# avga_final.net
KiCad netlist of a schematic drawn in EAGLE
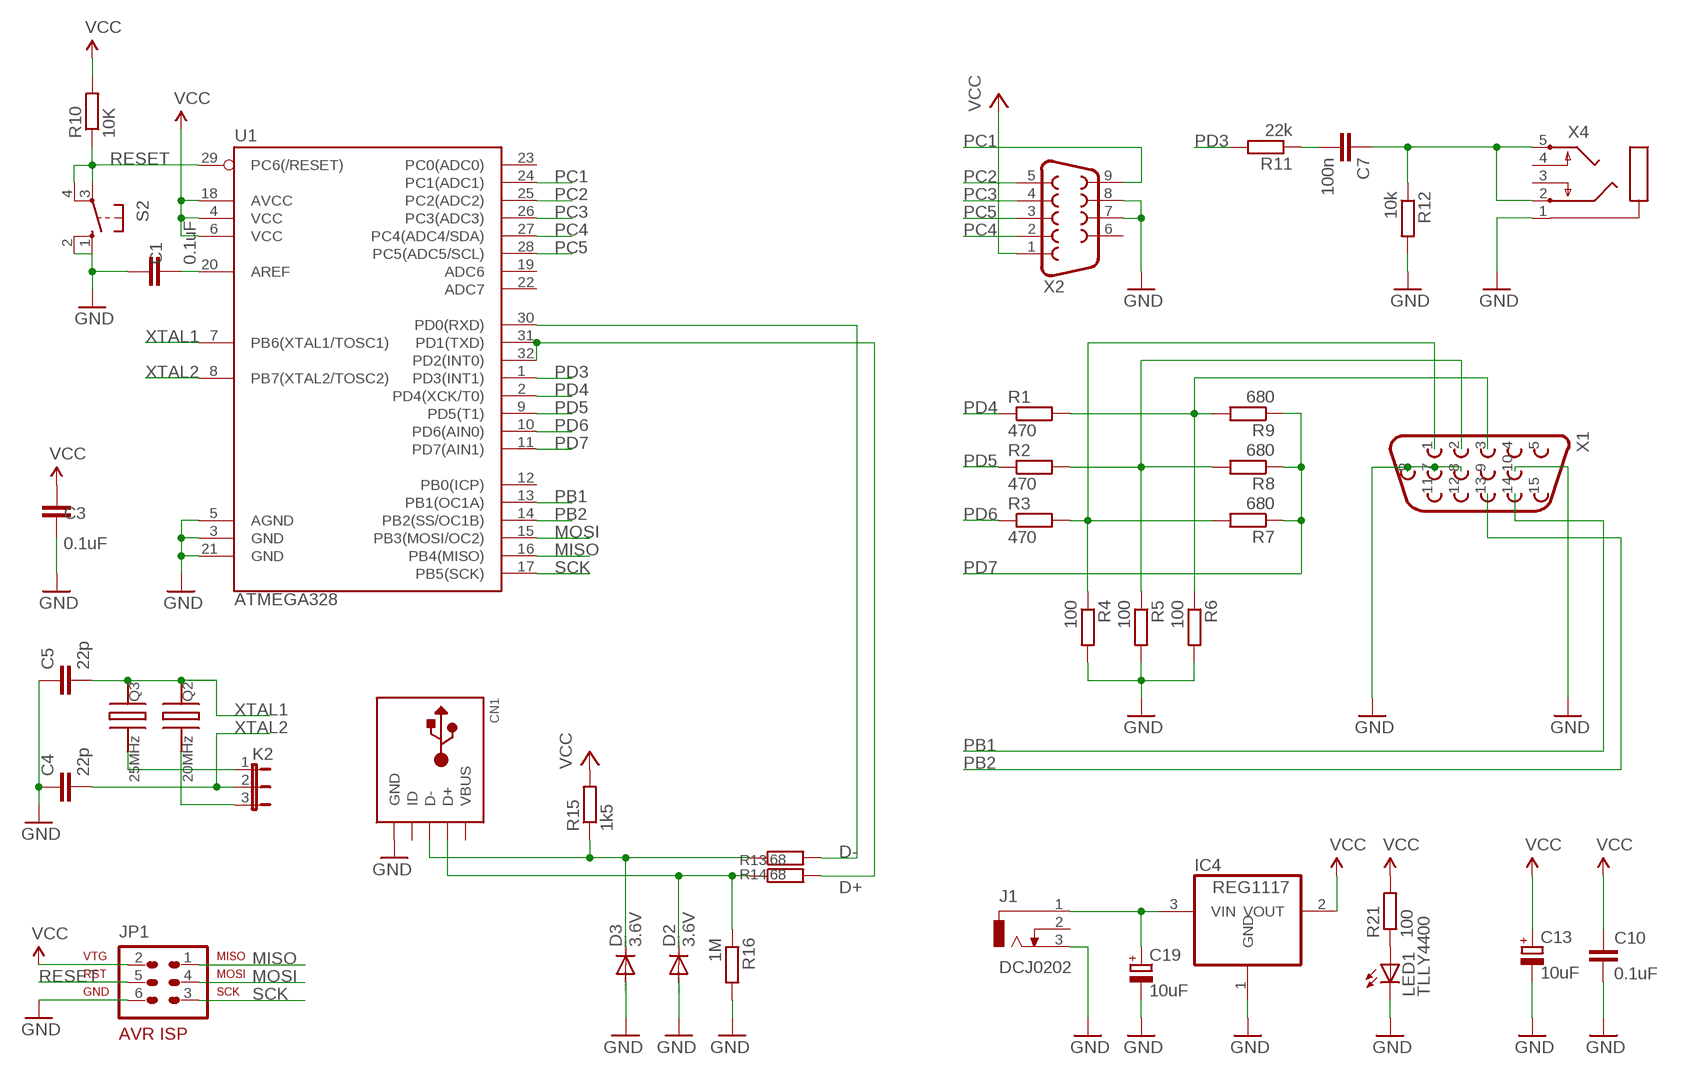
[diagram p0: schematic, sheet 1]

(export (version "E")
  (design (tool "Eeschema 10.0.6"))
  (components
    (comp (ref "C1")
      (value "0.1uF")
      (footprint "eagle-import:C0805")
      (libsource (lib "eagle-import") (part "resistor_C-EUC0805"))
    )
    (comp (ref "C3")
      (value "0.1uF")
      (footprint "eagle-import:C0805")
      (libsource (lib "eagle-import") (part "resistor_C-EUC0805"))
    )
    (comp (ref "C4")
      (value "22p")
      (footprint "eagle-import:C0805")
      (libsource (lib "eagle-import") (part "C-EUC0805"))
    )
    (comp (ref "C5")
      (value "22p")
      (footprint "eagle-import:C0805")
      (libsource (lib "eagle-import") (part "C-EUC0805"))
    )
    (comp (ref "C7")
      (value "100n")
      (footprint "eagle-import:C0805")
      (libsource (lib "eagle-import") (part "C-EUC0805"))
    )
    (comp (ref "C10")
      (value "0.1uF")
      (footprint "eagle-import:C0805")
      (libsource (lib "eagle-import") (part "C-EUC0805"))
    )
    (comp (ref "C13")
      (value "10uF")
      (footprint "eagle-import:E2,5-5")
      (libsource (lib "eagle-import") (part "CPOL-EUE2.5-5"))
    )
    (comp (ref "C19")
      (value "10uF")
      (footprint "eagle-import:E2,5-5")
      (libsource (lib "eagle-import") (part "CPOL-EUE2.5-5"))
    )
    (comp (ref "CN1")
      (value "USBMINIB")
      (footprint "eagle-import:USB-MINIB")
      (libsource (lib "eagle-import") (part "USBMINIB"))
    )
    (comp (ref "D2")
      (value "3.6V")
      (footprint "eagle-import:MINIMELF")
      (libsource (lib "eagle-import") (part "DIODE-MINIMELF"))
    )
    (comp (ref "D3")
      (value "3.6V")
      (footprint "eagle-import:MINIMELF")
      (libsource (lib "eagle-import") (part "DIODE-MINIMELF"))
    )
    (comp (ref "IC4")
      (value "REG1117")
      (footprint "eagle-import:SOT223")
      (libsource (lib "eagle-import") (part "REG1117"))
    )
    (comp (ref "J1")
      (value "DCJ0202")
      (footprint "eagle-import:DCJ0202")
      (libsource (lib "eagle-import") (part "DCJ0202"))
    )
    (comp (ref "JP1")
      (value "AVR-ISP-6R")
      (footprint "eagle-import:AVR-ISP-6R")
      (libsource (lib "eagle-import") (part "AVR-ISP-6R"))
    )
    (comp (ref "K2")
      (value "CON-3-POL")
      (footprint "eagle-import:MOLEX-PSK-03")
      (libsource (lib "eagle-import") (part "CON-3-POL"))
    )
    (comp (ref "LED1")
      (value "TLLY4400")
      (footprint "eagle-import:LED3MM")
      (fields (field (name "MF") "VISHAY SEMICONDUCTOR"))
      (libsource (lib "eagle-import") (part "TLLY4400"))
    )
    (comp (ref "Q2")
      (value "20MHz")
      (footprint "eagle-import:QUARZ")
      (libsource (lib "eagle-import") (part "QUARZ"))
    )
    (comp (ref "Q3")
      (value "25MHz")
      (footprint "eagle-import:QUARZ")
      (libsource (lib "eagle-import") (part "QUARZ"))
    )
    (comp (ref "R1")
      (value "470")
      (footprint "eagle-import:R0805")
      (libsource (lib "eagle-import") (part "R-EU_R0805"))
    )
    (comp (ref "R2")
      (value "470")
      (footprint "eagle-import:R0805")
      (libsource (lib "eagle-import") (part "R-EU_R0805"))
    )
    (comp (ref "R3")
      (value "470")
      (footprint "eagle-import:R0805")
      (libsource (lib "eagle-import") (part "R-EU_R0805"))
    )
    (comp (ref "R4")
      (value "100")
      (footprint "eagle-import:R0805")
      (libsource (lib "eagle-import") (part "R-EU_R0805"))
    )
    (comp (ref "R5")
      (value "100")
      (footprint "eagle-import:R0805")
      (libsource (lib "eagle-import") (part "R-EU_R0805"))
    )
    (comp (ref "R6")
      (value "100")
      (footprint "eagle-import:R0805")
      (libsource (lib "eagle-import") (part "R-EU_R0805"))
    )
    (comp (ref "R7")
      (value "680")
      (footprint "eagle-import:R0805")
      (libsource (lib "eagle-import") (part "R-EU_R0805"))
    )
    (comp (ref "R8")
      (value "680")
      (footprint "eagle-import:R0805")
      (libsource (lib "eagle-import") (part "R-EU_R0805"))
    )
    (comp (ref "R9")
      (value "680")
      (footprint "eagle-import:R0805")
      (libsource (lib "eagle-import") (part "R-EU_R0805"))
    )
    (comp (ref "R10")
      (value "10K")
      (footprint "eagle-import:R0805")
      (libsource (lib "eagle-import") (part "resistor_R-EU_R0805"))
    )
    (comp (ref "R11")
      (value "22k")
      (footprint "eagle-import:R0805")
      (libsource (lib "eagle-import") (part "R-EU_R0805"))
    )
    (comp (ref "R12")
      (value "10k")
      (footprint "eagle-import:R0805")
      (libsource (lib "eagle-import") (part "R-EU_R0805"))
    )
    (comp (ref "R13")
      (value "68")
      (footprint "eagle-import:R0805")
      (libsource (lib "eagle-import") (part "R-EU_R0805"))
    )
    (comp (ref "R14")
      (value "68")
      (footprint "eagle-import:R0805")
      (libsource (lib "eagle-import") (part "R-EU_R0805"))
    )
    (comp (ref "R15")
      (value "1k5")
      (footprint "eagle-import:R0805")
      (libsource (lib "eagle-import") (part "R-EU_R0805"))
    )
    (comp (ref "R16")
      (value "1M")
      (footprint "eagle-import:R0805")
      (libsource (lib "eagle-import") (part "R-EU_R0805"))
    )
    (comp (ref "R21")
      (value "100")
      (footprint "eagle-import:R0805")
      (libsource (lib "eagle-import") (part "resistor_R-EU_R0805"))
    )
    (comp (ref "S2")
      (value "10-XX")
      (footprint "eagle-import:B3F-10XX")
      (fields (field (name "MPN") "B3F-1000"))
      (libsource (lib "eagle-import") (part "10-XX"))
    )
    (comp (ref "U1")
      (value "ATMEGA328")
      (footprint "eagle-import:TQFP32-08")
      (libsource (lib "eagle-import") (part "ATMEGA168"))
    )
    (comp (ref "X1")
      (value "VGA-BU-15POL")
      (footprint "eagle-import:VGA-BU-15POL")
      (libsource (lib "eagle-import") (part "VGA-BU-15POL"))
    )
    (comp (ref "X2")
      (value "D-SUB-ST-9POL")
      (footprint "eagle-import:M09HP")
      (libsource (lib "eagle-import") (part "D-SUB-ST-9POL"))
    )
    (comp (ref "X4")
      (value "KLINKENBUCHSE")
      (footprint "eagle-import:KLINKENBUCHSE")
      (libsource (lib "eagle-import") (part "KLINKENBUCHSE"))
    )
  )
  (nets
    (net (code "1") (name "/MISO") (class "Default")
      (node (ref "JP1") (pin "1") (pinfunction "1_1") (pintype "passive"))
      (node (ref "U1") (pin "16") (pinfunction "PB4(MISO)_16") (pintype "bidirectional"))
    )
    (net (code "2") (name "/MOSI") (class "Default")
      (node (ref "JP1") (pin "4") (pinfunction "4_4") (pintype "passive"))
      (node (ref "U1") (pin "15") (pinfunction "PB3(MOSI/OC2)_15") (pintype "bidirectional"))
    )
    (net (code "3") (name "/PB1") (class "Default")
      (node (ref "U1") (pin "13") (pinfunction "PB1(OC1A)_13") (pintype "bidirectional"))
      (node (ref "X1") (pin "14") (pinfunction "14_14") (pintype "passive"))
    )
    (net (code "4") (name "/PB2") (class "Default")
      (node (ref "U1") (pin "14") (pinfunction "PB2(SS/OC1B)_14") (pintype "bidirectional"))
      (node (ref "X1") (pin "13") (pinfunction "13_13") (pintype "passive"))
    )
    (net (code "5") (name "/PC1") (class "Default")
      (node (ref "U1") (pin "24") (pinfunction "PC1(ADC1)_24") (pintype "bidirectional"))
      (node (ref "X2") (pin "9") (pinfunction "9_9") (pintype "passive"))
    )
    (net (code "6") (name "/PC2") (class "Default")
      (node (ref "U1") (pin "25") (pinfunction "PC2(ADC2)_25") (pintype "bidirectional"))
      (node (ref "X2") (pin "5") (pinfunction "5_5") (pintype "passive"))
    )
    (net (code "7") (name "/PC3") (class "Default")
      (node (ref "U1") (pin "26") (pinfunction "PC3(ADC3)_26") (pintype "bidirectional"))
      (node (ref "X2") (pin "4") (pinfunction "4_4") (pintype "passive"))
    )
    (net (code "8") (name "/PC4") (class "Default")
      (node (ref "U1") (pin "27") (pinfunction "PC4(ADC4/SDA)_27") (pintype "bidirectional"))
      (node (ref "X2") (pin "2") (pinfunction "2_2") (pintype "passive"))
    )
    (net (code "9") (name "/PC5") (class "Default")
      (node (ref "U1") (pin "28") (pinfunction "PC5(ADC5/SCL)_28") (pintype "bidirectional"))
      (node (ref "X2") (pin "3") (pinfunction "3_3") (pintype "passive"))
    )
    (net (code "10") (name "/PD3") (class "Default")
      (node (ref "R11") (pin "2") (pinfunction "2_2") (pintype "passive"))
      (node (ref "U1") (pin "1") (pinfunction "PD3(INT1)_1") (pintype "bidirectional"))
    )
    (net (code "11") (name "/PD4") (class "Default")
      (node (ref "R1") (pin "1") (pinfunction "1_1") (pintype "passive"))
      (node (ref "U1") (pin "2") (pinfunction "PD4(XCK/T0)_2") (pintype "bidirectional"))
    )
    (net (code "12") (name "/PD5") (class "Default")
      (node (ref "R2") (pin "1") (pinfunction "1_1") (pintype "passive"))
      (node (ref "U1") (pin "9") (pinfunction "PD5(T1)_9") (pintype "bidirectional"))
    )
    (net (code "13") (name "/PD6") (class "Default")
      (node (ref "R3") (pin "1") (pinfunction "1_1") (pintype "passive"))
      (node (ref "U1") (pin "10") (pinfunction "PD6(AIN0)_10") (pintype "bidirectional"))
    )
    (net (code "14") (name "/PD7") (class "Default")
      (node (ref "R7") (pin "1") (pinfunction "1_1") (pintype "passive"))
      (node (ref "R8") (pin "1") (pinfunction "1_1") (pintype "passive"))
      (node (ref "R9") (pin "1") (pinfunction "1_1") (pintype "passive"))
      (node (ref "U1") (pin "11") (pinfunction "PD7(AIN1)_11") (pintype "bidirectional"))
    )
    (net (code "15") (name "/RESET") (class "Default")
      (node (ref "JP1") (pin "5") (pinfunction "5_5") (pintype "passive"))
      (node (ref "R10") (pin "1") (pinfunction "1_1") (pintype "passive"))
      (node (ref "S2") (pin "3") (pinfunction "P_3") (pintype "passive"))
      (node (ref "S2") (pin "4") (pinfunction "P1_4") (pintype "passive"))
      (node (ref "U1") (pin "29") (pinfunction "PC6(/RESET)_29") (pintype "bidirectional"))
    )
    (net (code "16") (name "/SCK") (class "Default")
      (node (ref "JP1") (pin "3") (pinfunction "3_3") (pintype "passive"))
      (node (ref "U1") (pin "17") (pinfunction "PB5(SCK)_17") (pintype "bidirectional"))
    )
    (net (code "17") (name "/VBUS") (class "Default")
      (node (ref "CN1") (pin "VBUS") (pinfunction "VBUS_VBUS") (pintype "power_in"))
    )
    (net (code "18") (name "/XTAL1") (class "Default")
      (node (ref "C5") (pin "2") (pinfunction "2_2") (pintype "passive"))
      (node (ref "Q2") (pin "1") (pinfunction "1_1") (pintype "passive"))
      (node (ref "Q3") (pin "1") (pinfunction "1_1") (pintype "passive"))
      (node (ref "U1") (pin "7") (pinfunction "PB6(XTAL1/TOSC1)_7") (pintype "bidirectional"))
    )
    (net (code "19") (name "/XTAL2") (class "Default")
      (node (ref "C4") (pin "2") (pinfunction "2_2") (pintype "passive"))
      (node (ref "K2") (pin "2") (pinfunction "2_2") (pintype "passive"))
      (node (ref "U1") (pin "8") (pinfunction "PB7(XTAL2/TOSC2)_8") (pintype "bidirectional"))
    )
    (net (code "20") (name "GND") (class "Default")
      (node (ref "C1") (pin "2") (pinfunction "2_2") (pintype "passive"))
      (node (ref "C10") (pin "2") (pinfunction "2_2") (pintype "passive"))
      (node (ref "C13") (pin "-") (pinfunction "-_-") (pintype "passive"))
      (node (ref "C19") (pin "-") (pinfunction "-_-") (pintype "passive"))
      (node (ref "C3") (pin "1") (pinfunction "1_1") (pintype "passive"))
      (node (ref "C4") (pin "1") (pinfunction "1_1") (pintype "passive"))
      (node (ref "C5") (pin "1") (pinfunction "1_1") (pintype "passive"))
      (node (ref "CN1") (pin "GND") (pinfunction "GND_GND") (pintype "power_in"))
      (node (ref "D2") (pin "A") (pinfunction "A_A") (pintype "passive"))
      (node (ref "D3") (pin "A") (pinfunction "A_A") (pintype "passive"))
      (node (ref "IC4") (pin "1") (pinfunction "GND_1") (pintype "power_in"))
      (node (ref "J1") (pin "3") (pinfunction "3_3") (pintype "passive"))
      (node (ref "JP1") (pin "6") (pinfunction "6_6") (pintype "passive"))
      (node (ref "LED1") (pin "K") (pinfunction "C_K") (pintype "passive"))
      (node (ref "R12") (pin "2") (pinfunction "2_2") (pintype "passive"))
      (node (ref "R16") (pin "2") (pinfunction "2_2") (pintype "passive"))
      (node (ref "R4") (pin "2") (pinfunction "2_2") (pintype "passive"))
      (node (ref "R5") (pin "2") (pinfunction "2_2") (pintype "passive"))
      (node (ref "R6") (pin "2") (pinfunction "2_2") (pintype "passive"))
      (node (ref "S2") (pin "1") (pinfunction "S_1") (pintype "passive"))
      (node (ref "S2") (pin "2") (pinfunction "S1_2") (pintype "passive"))
      (node (ref "U1") (pin "21") (pinfunction "GND_21") (pintype "bidirectional"))
      (node (ref "U1") (pin "3") (pinfunction "GND_3") (pintype "bidirectional"))
      (node (ref "U1") (pin "5") (pinfunction "AGND_5") (pintype "bidirectional"))
      (node (ref "X1") (pin "10") (pinfunction "10_10") (pintype "passive"))
      (node (ref "X1") (pin "6") (pinfunction "6_6") (pintype "passive"))
      (node (ref "X1") (pin "7") (pinfunction "7_7") (pintype "passive"))
      (node (ref "X1") (pin "8") (pinfunction "8_8") (pintype "passive"))
      (node (ref "X2") (pin "7") (pinfunction "7_7") (pintype "passive"))
      (node (ref "X2") (pin "8") (pinfunction "8_8") (pintype "passive"))
      (node (ref "X4") (pin "1") (pinfunction "1_1") (pintype "passive"))
    )
    (net (code "21") (name "Net-(C7-Pad1)") (class "Default")
      (node (ref "C7") (pin "1") (pinfunction "1_1") (pintype "passive"))
      (node (ref "R12") (pin "1") (pinfunction "1_1") (pintype "passive"))
      (node (ref "X4") (pin "2") (pinfunction "2_2") (pintype "passive"))
      (node (ref "X4") (pin "5") (pinfunction "5_5") (pintype "passive"))
    )
    (net (code "22") (name "Net-(C7-Pad2)") (class "Default")
      (node (ref "C7") (pin "2") (pinfunction "2_2") (pintype "passive"))
      (node (ref "R11") (pin "1") (pinfunction "1_1") (pintype "passive"))
    )
    (net (code "23") (name "Net-(CN1-PadD+)") (class "Default")
      (node (ref "CN1") (pin "D+") (pinfunction "D+_D+") (pintype "bidirectional"))
      (node (ref "D2") (pin "C") (pinfunction "C_C") (pintype "passive"))
      (node (ref "R13") (pin "1") (pinfunction "1_1") (pintype "passive"))
      (node (ref "R16") (pin "1") (pinfunction "1_1") (pintype "passive"))
    )
    (net (code "24") (name "Net-(CN1-PadD-)") (class "Default")
      (node (ref "CN1") (pin "D-") (pinfunction "D-_D-") (pintype "bidirectional"))
      (node (ref "D3") (pin "C") (pinfunction "C_C") (pintype "passive"))
      (node (ref "R14") (pin "1") (pinfunction "1_1") (pintype "passive"))
      (node (ref "R15") (pin "1") (pinfunction "1_1") (pintype "passive"))
    )
    (net (code "25") (name "Net-(IC4-VIN)") (class "Default")
      (node (ref "C19") (pin "+") (pinfunction "+_+") (pintype "passive"))
      (node (ref "IC4") (pin "3") (pinfunction "VIN_3") (pintype "input"))
      (node (ref "J1") (pin "1") (pinfunction "1_1") (pintype "passive"))
    )
    (net (code "26") (name "Net-(K2-Pad1)") (class "Default")
      (node (ref "K2") (pin "1") (pinfunction "1_1") (pintype "passive"))
      (node (ref "Q3") (pin "2") (pinfunction "2_2") (pintype "passive"))
    )
    (net (code "27") (name "Net-(K2-Pad3)") (class "Default")
      (node (ref "K2") (pin "3") (pinfunction "3_3") (pintype "passive"))
      (node (ref "Q2") (pin "2") (pinfunction "2_2") (pintype "passive"))
    )
    (net (code "28") (name "Net-(LED1-PadA)") (class "Default")
      (node (ref "LED1") (pin "A") (pinfunction "A_A") (pintype "passive"))
      (node (ref "R21") (pin "1") (pinfunction "1_1") (pintype "passive"))
    )
    (net (code "29") (name "Net-(R1-Pad2)") (class "Default")
      (node (ref "R1") (pin "2") (pinfunction "2_2") (pintype "passive"))
      (node (ref "R6") (pin "1") (pinfunction "1_1") (pintype "passive"))
      (node (ref "R9") (pin "2") (pinfunction "2_2") (pintype "passive"))
      (node (ref "X1") (pin "3") (pinfunction "3_3") (pintype "passive"))
    )
    (net (code "30") (name "Net-(R2-Pad2)") (class "Default")
      (node (ref "R2") (pin "2") (pinfunction "2_2") (pintype "passive"))
      (node (ref "R5") (pin "1") (pinfunction "1_1") (pintype "passive"))
      (node (ref "R8") (pin "2") (pinfunction "2_2") (pintype "passive"))
      (node (ref "X1") (pin "2") (pinfunction "2_2") (pintype "passive"))
    )
    (net (code "31") (name "Net-(R3-Pad2)") (class "Default")
      (node (ref "R3") (pin "2") (pinfunction "2_2") (pintype "passive"))
      (node (ref "R4") (pin "1") (pinfunction "1_1") (pintype "passive"))
      (node (ref "R7") (pin "2") (pinfunction "2_2") (pintype "passive"))
      (node (ref "X1") (pin "1") (pinfunction "1_1") (pintype "passive"))
    )
    (net (code "32") (name "Net-(U1-AREF)") (class "Default")
      (node (ref "C1") (pin "1") (pinfunction "1_1") (pintype "passive"))
      (node (ref "U1") (pin "20") (pinfunction "AREF_20") (pintype "bidirectional"))
    )
    (net (code "33") (name "Net-(U1-PD0(RXD))") (class "Default")
      (node (ref "R14") (pin "2") (pinfunction "2_2") (pintype "passive"))
      (node (ref "U1") (pin "30") (pinfunction "PD0(RXD)_30") (pintype "bidirectional"))
    )
    (net (code "34") (name "Net-(U1-PD1(TXD))") (class "Default")
      (node (ref "R13") (pin "2") (pinfunction "2_2") (pintype "passive"))
      (node (ref "U1") (pin "31") (pinfunction "PD1(TXD)_31") (pintype "bidirectional"))
      (node (ref "U1") (pin "32") (pinfunction "PD2(INT0)_32") (pintype "bidirectional"))
    )
    (net (code "35") (name "VCC") (class "Default")
      (node (ref "C10") (pin "1") (pinfunction "1_1") (pintype "passive"))
      (node (ref "C13") (pin "+") (pinfunction "+_+") (pintype "passive"))
      (node (ref "C3") (pin "2") (pinfunction "2_2") (pintype "passive"))
      (node (ref "IC4") (pin "2") (pinfunction "VOUT_2") (pintype "output"))
      (node (ref "JP1") (pin "2") (pinfunction "2_2") (pintype "passive"))
      (node (ref "R10") (pin "2") (pinfunction "2_2") (pintype "passive"))
      (node (ref "R15") (pin "2") (pinfunction "2_2") (pintype "passive"))
      (node (ref "R21") (pin "2") (pinfunction "2_2") (pintype "passive"))
      (node (ref "U1") (pin "18") (pinfunction "AVCC_18") (pintype "bidirectional"))
      (node (ref "U1") (pin "4") (pinfunction "VCC_4") (pintype "bidirectional"))
      (node (ref "U1") (pin "6") (pinfunction "VCC_6") (pintype "bidirectional"))
      (node (ref "X2") (pin "1") (pinfunction "1_1") (pintype "passive"))
    )
    (net (code "36") (name "unconnected-(CN1-PadID)") (class "Default")
      (node (ref "CN1") (pin "ID") (pinfunction "ID_ID") (pintype "bidirectional"))
    )
    (net (code "37") (name "unconnected-(J1-Pad2)") (class "Default")
      (node (ref "J1") (pin "2") (pinfunction "2_2") (pintype "passive"))
    )
    (net (code "38") (name "unconnected-(U1-ADC6-Pad19)") (class "Default")
      (node (ref "U1") (pin "19") (pinfunction "ADC6_19") (pintype "bidirectional"))
    )
    (net (code "39") (name "unconnected-(U1-ADC7-Pad22)") (class "Default")
      (node (ref "U1") (pin "22") (pinfunction "ADC7_22") (pintype "bidirectional"))
    )
    (net (code "40") (name "unconnected-(U1-PB0(ICP)-Pad12)") (class "Default")
      (node (ref "U1") (pin "12") (pinfunction "PB0(ICP)_12") (pintype "bidirectional"))
    )
    (net (code "41") (name "unconnected-(U1-PC0(ADC0)-Pad23)") (class "Default")
      (node (ref "U1") (pin "23") (pinfunction "PC0(ADC0)_23") (pintype "bidirectional"))
    )
    (net (code "42") (name "unconnected-(X1-Pad4)") (class "Default")
      (node (ref "X1") (pin "4") (pinfunction "4_4") (pintype "passive"))
    )
    (net (code "43") (name "unconnected-(X1-Pad5)") (class "Default")
      (node (ref "X1") (pin "5") (pinfunction "5_5") (pintype "passive"))
    )
    (net (code "44") (name "unconnected-(X1-Pad9)") (class "Default")
      (node (ref "X1") (pin "9") (pinfunction "9_9") (pintype "passive"))
    )
    (net (code "45") (name "unconnected-(X1-Pad11)") (class "Default")
      (node (ref "X1") (pin "11") (pinfunction "11_11") (pintype "passive"))
    )
    (net (code "46") (name "unconnected-(X1-Pad12)") (class "Default")
      (node (ref "X1") (pin "12") (pinfunction "12_12") (pintype "passive"))
    )
    (net (code "47") (name "unconnected-(X1-Pad15)") (class "Default")
      (node (ref "X1") (pin "15") (pinfunction "15_15") (pintype "passive"))
    )
    (net (code "48") (name "unconnected-(X2-Pad6)") (class "Default")
      (node (ref "X2") (pin "6") (pinfunction "6_6") (pintype "passive"))
    )
    (net (code "49") (name "unconnected-(X4-Pad3)") (class "Default")
      (node (ref "X4") (pin "3") (pinfunction "3_3") (pintype "passive"))
    )
    (net (code "50") (name "unconnected-(X4-Pad4)") (class "Default")
      (node (ref "X4") (pin "4") (pinfunction "4_4") (pintype "passive"))
    )
  )
)
